# EMG.net
KiCad netlist of a schematic drawn in EAGLE
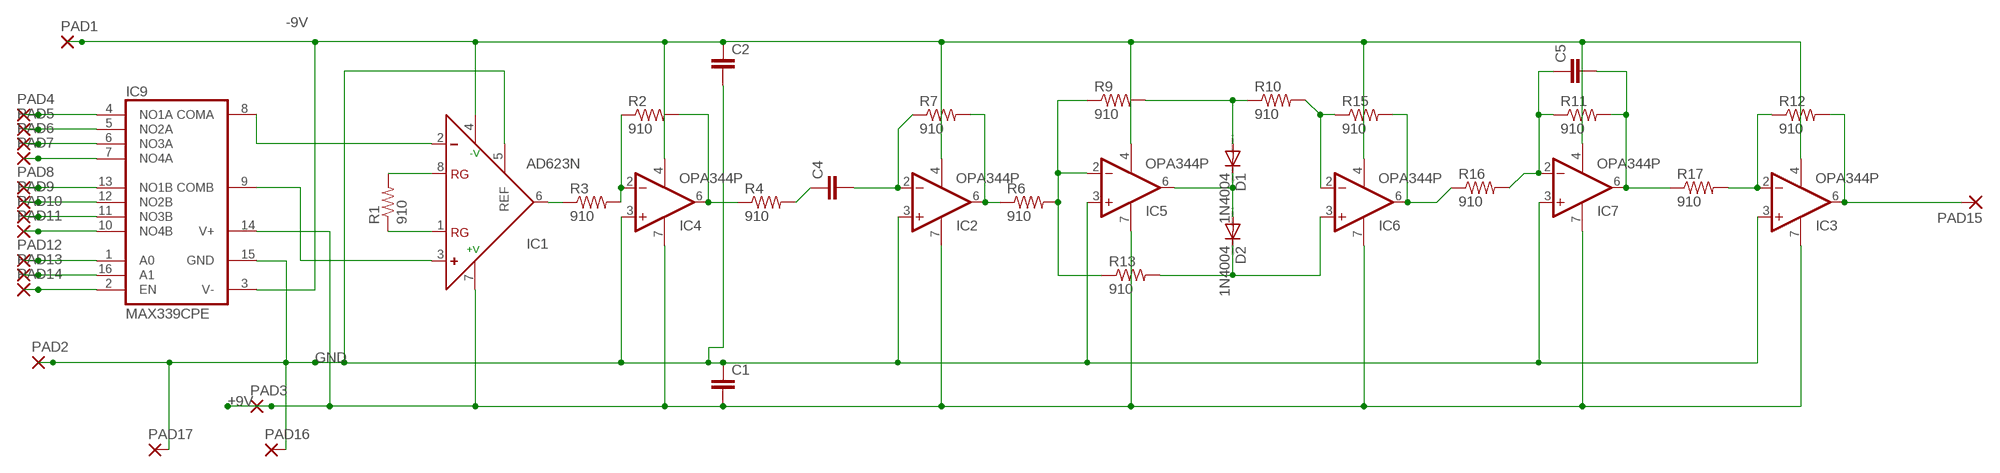
[diagram p0: schematic, sheet 1]

(export (version "E")
  (design (tool "Eeschema 10.0.6"))
  (components
    (comp (ref "C1")
      (value "C2,5-3")
      (footprint "eagle-import:C2.5-3")
      (libsource (lib "eagle-import") (part "C2,5-3"))
    )
    (comp (ref "C2")
      (value "C2,5-3")
      (footprint "eagle-import:C2.5-3")
      (libsource (lib "eagle-import") (part "C2,5-3"))
    )
    (comp (ref "C4")
      (value "C2,5-3")
      (footprint "eagle-import:C2.5-3")
      (libsource (lib "eagle-import") (part "C2,5-3"))
    )
    (comp (ref "C5")
      (value "C2,5-3")
      (footprint "eagle-import:C2.5-3")
      (libsource (lib "eagle-import") (part "C2,5-3"))
    )
    (comp (ref "D1")
      (value "1N4004")
      (footprint "eagle-import:DO41-10")
      (libsource (lib "eagle-import") (part "1N4004"))
    )
    (comp (ref "D2")
      (value "1N4004")
      (footprint "eagle-import:DO41-10")
      (libsource (lib "eagle-import") (part "1N4004"))
    )
    (comp (ref "IC1")
      (value "AD623N")
      (footprint "eagle-import:DIL08")
      (fields (field (name "MF") "ALTERA CORPORATION") (field (name "MPN") "AD623ANZ"))
      (libsource (lib "eagle-import") (part "AD623N"))
    )
    (comp (ref "IC2")
      (value "OPA344P")
      (footprint "eagle-import:DIL08")
      (libsource (lib "eagle-import") (part "OPAP344"))
    )
    (comp (ref "IC3")
      (value "OPA344P")
      (footprint "eagle-import:DIL08")
      (libsource (lib "eagle-import") (part "OPAP344"))
    )
    (comp (ref "IC4")
      (value "OPA344P")
      (footprint "eagle-import:DIL08")
      (libsource (lib "eagle-import") (part "OPAP344"))
    )
    (comp (ref "IC5")
      (value "OPA344P")
      (footprint "eagle-import:DIL08")
      (libsource (lib "eagle-import") (part "OPAP344"))
    )
    (comp (ref "IC6")
      (value "OPA344P")
      (footprint "eagle-import:DIL08")
      (libsource (lib "eagle-import") (part "OPAP344"))
    )
    (comp (ref "IC7")
      (value "OPA344P")
      (footprint "eagle-import:DIL08")
      (libsource (lib "eagle-import") (part "OPAP344"))
    )
    (comp (ref "IC9")
      (value "MAX339CPE")
      (footprint "eagle-import:DIL16")
      (fields (field (name "MPN") "MAX339CPE+"))
      (libsource (lib "eagle-import") (part "MAX339CPE"))
    )
    (comp (ref "PAD1")
      (value "2,15/1,0")
      (footprint "eagle-import:2,15_1,0")
      (libsource (lib "eagle-import") (part "2,15/1,0"))
    )
    (comp (ref "PAD2")
      (value "2,15/1,0")
      (footprint "eagle-import:2,15_1,0")
      (libsource (lib "eagle-import") (part "2,15/1,0"))
    )
    (comp (ref "PAD3")
      (value "2,15/1,0")
      (footprint "eagle-import:2,15_1,0")
      (libsource (lib "eagle-import") (part "2,15/1,0"))
    )
    (comp (ref "PAD4")
      (value "2,15/1,0")
      (footprint "eagle-import:2,15_1,0")
      (libsource (lib "eagle-import") (part "2,15/1,0"))
    )
    (comp (ref "PAD5")
      (value "2,15/1,0")
      (footprint "eagle-import:2,15_1,0")
      (libsource (lib "eagle-import") (part "2,15/1,0"))
    )
    (comp (ref "PAD6")
      (value "2,15/1,0")
      (footprint "eagle-import:2,15_1,0")
      (libsource (lib "eagle-import") (part "2,15/1,0"))
    )
    (comp (ref "PAD7")
      (value "2,15/1,0")
      (footprint "eagle-import:2,15_1,0")
      (libsource (lib "eagle-import") (part "2,15/1,0"))
    )
    (comp (ref "PAD8")
      (value "2,15/1,0")
      (footprint "eagle-import:2,15_1,0")
      (libsource (lib "eagle-import") (part "2,15/1,0"))
    )
    (comp (ref "PAD9")
      (value "2,15/1,0")
      (footprint "eagle-import:2,15_1,0")
      (libsource (lib "eagle-import") (part "2,15/1,0"))
    )
    (comp (ref "PAD10")
      (value "2,15/1,0")
      (footprint "eagle-import:2,15_1,0")
      (libsource (lib "eagle-import") (part "2,15/1,0"))
    )
    (comp (ref "PAD11")
      (value "2,15/1,0")
      (footprint "eagle-import:2,15_1,0")
      (libsource (lib "eagle-import") (part "2,15/1,0"))
    )
    (comp (ref "PAD12")
      (value "2,15/1,0")
      (footprint "eagle-import:2,15_1,0")
      (libsource (lib "eagle-import") (part "2,15/1,0"))
    )
    (comp (ref "PAD13")
      (value "2,15/1,0")
      (footprint "eagle-import:2,15_1,0")
      (libsource (lib "eagle-import") (part "2,15/1,0"))
    )
    (comp (ref "PAD14")
      (value "2,15/1,0")
      (footprint "eagle-import:2,15_1,0")
      (libsource (lib "eagle-import") (part "2,15/1,0"))
    )
    (comp (ref "PAD15")
      (value "2,15/1,0")
      (footprint "eagle-import:2,15_1,0")
      (libsource (lib "eagle-import") (part "2,15/1,0"))
    )
    (comp (ref "PAD16")
      (value "2,15/1,0")
      (footprint "eagle-import:2,15_1,0")
      (libsource (lib "eagle-import") (part "2,15/1,0"))
    )
    (comp (ref "PAD17")
      (value "2,15/1,0")
      (footprint "eagle-import:2,15_1,0")
      (libsource (lib "eagle-import") (part "2,15/1,0"))
    )
    (comp (ref "R1")
      (value "910")
      (footprint "eagle-import:0204_7")
      (libsource (lib "eagle-import") (part "R-US_0204/7"))
    )
    (comp (ref "R2")
      (value "910")
      (footprint "eagle-import:0204_7")
      (libsource (lib "eagle-import") (part "R-US_0204/7"))
    )
    (comp (ref "R3")
      (value "910")
      (footprint "eagle-import:0204_7")
      (libsource (lib "eagle-import") (part "R-US_0204/7"))
    )
    (comp (ref "R4")
      (value "910")
      (footprint "eagle-import:0204_7")
      (libsource (lib "eagle-import") (part "R-US_0204/7"))
    )
    (comp (ref "R6")
      (value "910")
      (footprint "eagle-import:0204_7")
      (libsource (lib "eagle-import") (part "R-US_0204/7"))
    )
    (comp (ref "R7")
      (value "910")
      (footprint "eagle-import:0204_7")
      (libsource (lib "eagle-import") (part "R-US_0204/7"))
    )
    (comp (ref "R9")
      (value "910")
      (footprint "eagle-import:0204_7")
      (libsource (lib "eagle-import") (part "R-US_0204/7"))
    )
    (comp (ref "R10")
      (value "910")
      (footprint "eagle-import:0204_7")
      (libsource (lib "eagle-import") (part "R-US_0204/7"))
    )
    (comp (ref "R11")
      (value "910")
      (footprint "eagle-import:0204_7")
      (libsource (lib "eagle-import") (part "R-US_0204/7"))
    )
    (comp (ref "R12")
      (value "910")
      (footprint "eagle-import:0204_7")
      (libsource (lib "eagle-import") (part "R-US_0204/7"))
    )
    (comp (ref "R13")
      (value "910")
      (footprint "eagle-import:0204_7")
      (libsource (lib "eagle-import") (part "R-US_0204/7"))
    )
    (comp (ref "R15")
      (value "910")
      (footprint "eagle-import:0204_7")
      (libsource (lib "eagle-import") (part "R-US_0204/7"))
    )
    (comp (ref "R16")
      (value "910")
      (footprint "eagle-import:0204_7")
      (libsource (lib "eagle-import") (part "R-US_0204/7"))
    )
    (comp (ref "R17")
      (value "910")
      (footprint "eagle-import:0204_7")
      (libsource (lib "eagle-import") (part "R-US_0204/7"))
    )
  )
  (nets
    (net (code "1") (name "/+9V") (class "Default")
      (node (ref "C1") (pin "2") (pinfunction "2_2") (pintype "passive"))
      (node (ref "IC1") (pin "7") (pinfunction "+V_7") (pintype "power_in"))
      (node (ref "IC2") (pin "7") (pinfunction "V+_7") (pintype "power_in"))
      (node (ref "IC3") (pin "7") (pinfunction "V+_7") (pintype "power_in"))
      (node (ref "IC4") (pin "7") (pinfunction "V+_7") (pintype "power_in"))
      (node (ref "IC5") (pin "7") (pinfunction "V+_7") (pintype "power_in"))
      (node (ref "IC6") (pin "7") (pinfunction "V+_7") (pintype "power_in"))
      (node (ref "IC7") (pin "7") (pinfunction "V+_7") (pintype "power_in"))
      (node (ref "IC9") (pin "14") (pinfunction "V+_14") (pintype "power_in"))
      (node (ref "PAD3") (pin "1") (pinfunction "P_1") (pintype "passive"))
    )
    (net (code "2") (name "/-9V") (class "Default")
      (node (ref "C2") (pin "1") (pinfunction "1_1") (pintype "passive"))
      (node (ref "IC1") (pin "4") (pinfunction "-V_4") (pintype "power_in"))
      (node (ref "IC2") (pin "4") (pinfunction "V-_4") (pintype "power_in"))
      (node (ref "IC3") (pin "4") (pinfunction "V-_4") (pintype "power_in"))
      (node (ref "IC4") (pin "4") (pinfunction "V-_4") (pintype "power_in"))
      (node (ref "IC5") (pin "4") (pinfunction "V-_4") (pintype "power_in"))
      (node (ref "IC6") (pin "4") (pinfunction "V-_4") (pintype "power_in"))
      (node (ref "IC7") (pin "4") (pinfunction "V-_4") (pintype "power_in"))
      (node (ref "IC9") (pin "3") (pinfunction "V-_3") (pintype "power_in"))
      (node (ref "PAD1") (pin "1") (pinfunction "P_1") (pintype "passive"))
    )
    (net (code "3") (name "/GND") (class "Default")
      (node (ref "C1") (pin "1") (pinfunction "1_1") (pintype "passive"))
      (node (ref "C2") (pin "2") (pinfunction "2_2") (pintype "passive"))
      (node (ref "IC1") (pin "5") (pinfunction "REF_5") (pintype "passive"))
      (node (ref "IC2") (pin "3") (pinfunction "+IN_3") (pintype "input"))
      (node (ref "IC3") (pin "3") (pinfunction "+IN_3") (pintype "input"))
      (node (ref "IC4") (pin "3") (pinfunction "+IN_3") (pintype "input"))
      (node (ref "IC5") (pin "3") (pinfunction "+IN_3") (pintype "input"))
      (node (ref "IC7") (pin "3") (pinfunction "+IN_3") (pintype "input"))
      (node (ref "IC9") (pin "15") (pinfunction "GND_15") (pintype "power_in"))
      (node (ref "PAD16") (pin "1") (pinfunction "P_1") (pintype "passive"))
      (node (ref "PAD17") (pin "1") (pinfunction "P_1") (pintype "passive"))
      (node (ref "PAD2") (pin "1") (pinfunction "P_1") (pintype "passive"))
    )
    (net (code "4") (name "Net-(C4-Pad1)") (class "Default")
      (node (ref "C4") (pin "1") (pinfunction "1_1") (pintype "passive"))
      (node (ref "R4") (pin "2") (pinfunction "2_2") (pintype "passive"))
    )
    (net (code "5") (name "Net-(D1-PadA)") (class "Default")
      (node (ref "D1") (pin "A") (pinfunction "A_A") (pintype "passive"))
      (node (ref "R10") (pin "1") (pinfunction "1_1") (pintype "passive"))
      (node (ref "R9") (pin "2") (pinfunction "2_2") (pintype "passive"))
    )
    (net (code "6") (name "Net-(IC1-+)") (class "Default")
      (node (ref "IC1") (pin "3") (pinfunction "+_3") (pintype "input"))
      (node (ref "IC9") (pin "9") (pinfunction "COMB_9") (pintype "passive"))
    )
    (net (code "7") (name "Net-(IC1--)") (class "Default")
      (node (ref "IC1") (pin "2") (pinfunction "-_2") (pintype "input"))
      (node (ref "IC9") (pin "8") (pinfunction "COMA_8") (pintype "passive"))
    )
    (net (code "8") (name "Net-(IC1-OUT)") (class "Default")
      (node (ref "IC1") (pin "6") (pinfunction "OUT_6") (pintype "output"))
      (node (ref "R3") (pin "1") (pinfunction "1_1") (pintype "passive"))
    )
    (net (code "9") (name "Net-(IC1-RG-Pad1)") (class "Default")
      (node (ref "IC1") (pin "1") (pinfunction "RG_1") (pintype "passive"))
      (node (ref "R1") (pin "1") (pinfunction "1_1") (pintype "passive"))
    )
    (net (code "10") (name "Net-(IC1-RG-Pad8)") (class "Default")
      (node (ref "IC1") (pin "8") (pinfunction "RG_8") (pintype "passive"))
      (node (ref "R1") (pin "2") (pinfunction "2_2") (pintype "passive"))
    )
    (net (code "11") (name "Net-(IC2--IN)") (class "Default")
      (node (ref "C4") (pin "2") (pinfunction "2_2") (pintype "passive"))
      (node (ref "IC2") (pin "2") (pinfunction "-IN_2") (pintype "input"))
      (node (ref "R7") (pin "1") (pinfunction "1_1") (pintype "passive"))
    )
    (net (code "12") (name "Net-(IC2-OUT)") (class "Default")
      (node (ref "IC2") (pin "6") (pinfunction "OUT_6") (pintype "output"))
      (node (ref "R6") (pin "1") (pinfunction "1_1") (pintype "passive"))
      (node (ref "R7") (pin "2") (pinfunction "2_2") (pintype "passive"))
    )
    (net (code "13") (name "Net-(IC3--IN)") (class "Default")
      (node (ref "IC3") (pin "2") (pinfunction "-IN_2") (pintype "input"))
      (node (ref "R12") (pin "1") (pinfunction "1_1") (pintype "passive"))
      (node (ref "R17") (pin "2") (pinfunction "2_2") (pintype "passive"))
    )
    (net (code "14") (name "Net-(IC3-OUT)") (class "Default")
      (node (ref "IC3") (pin "6") (pinfunction "OUT_6") (pintype "output"))
      (node (ref "PAD15") (pin "1") (pinfunction "P_1") (pintype "passive"))
      (node (ref "R12") (pin "2") (pinfunction "2_2") (pintype "passive"))
    )
    (net (code "15") (name "Net-(IC4--IN)") (class "Default")
      (node (ref "IC4") (pin "2") (pinfunction "-IN_2") (pintype "input"))
      (node (ref "R2") (pin "1") (pinfunction "1_1") (pintype "passive"))
      (node (ref "R3") (pin "2") (pinfunction "2_2") (pintype "passive"))
    )
    (net (code "16") (name "Net-(IC4-OUT)") (class "Default")
      (node (ref "IC4") (pin "6") (pinfunction "OUT_6") (pintype "output"))
      (node (ref "R2") (pin "2") (pinfunction "2_2") (pintype "passive"))
      (node (ref "R4") (pin "1") (pinfunction "1_1") (pintype "passive"))
    )
    (net (code "17") (name "Net-(IC5--IN)") (class "Default")
      (node (ref "IC5") (pin "2") (pinfunction "-IN_2") (pintype "input"))
      (node (ref "R13") (pin "1") (pinfunction "1_1") (pintype "passive"))
      (node (ref "R6") (pin "2") (pinfunction "2_2") (pintype "passive"))
      (node (ref "R9") (pin "1") (pinfunction "1_1") (pintype "passive"))
    )
    (net (code "18") (name "Net-(IC5-OUT)") (class "Default")
      (node (ref "D1") (pin "C") (pinfunction "C_C") (pintype "passive"))
      (node (ref "D2") (pin "A") (pinfunction "A_A") (pintype "passive"))
      (node (ref "IC5") (pin "6") (pinfunction "OUT_6") (pintype "output"))
    )
    (net (code "19") (name "Net-(IC6-+IN)") (class "Default")
      (node (ref "D2") (pin "C") (pinfunction "C_C") (pintype "passive"))
      (node (ref "IC6") (pin "3") (pinfunction "+IN_3") (pintype "input"))
      (node (ref "R13") (pin "2") (pinfunction "2_2") (pintype "passive"))
    )
    (net (code "20") (name "Net-(IC6--IN)") (class "Default")
      (node (ref "IC6") (pin "2") (pinfunction "-IN_2") (pintype "input"))
      (node (ref "R10") (pin "2") (pinfunction "2_2") (pintype "passive"))
      (node (ref "R15") (pin "1") (pinfunction "1_1") (pintype "passive"))
    )
    (net (code "21") (name "Net-(IC6-OUT)") (class "Default")
      (node (ref "IC6") (pin "6") (pinfunction "OUT_6") (pintype "output"))
      (node (ref "R15") (pin "2") (pinfunction "2_2") (pintype "passive"))
      (node (ref "R16") (pin "1") (pinfunction "1_1") (pintype "passive"))
    )
    (net (code "22") (name "Net-(IC7--IN)") (class "Default")
      (node (ref "C5") (pin "1") (pinfunction "1_1") (pintype "passive"))
      (node (ref "IC7") (pin "2") (pinfunction "-IN_2") (pintype "input"))
      (node (ref "R11") (pin "1") (pinfunction "1_1") (pintype "passive"))
      (node (ref "R16") (pin "2") (pinfunction "2_2") (pintype "passive"))
    )
    (net (code "23") (name "Net-(IC7-OUT)") (class "Default")
      (node (ref "C5") (pin "2") (pinfunction "2_2") (pintype "passive"))
      (node (ref "IC7") (pin "6") (pinfunction "OUT_6") (pintype "output"))
      (node (ref "R11") (pin "2") (pinfunction "2_2") (pintype "passive"))
      (node (ref "R17") (pin "1") (pinfunction "1_1") (pintype "passive"))
    )
    (net (code "24") (name "Net-(IC9-A0)") (class "Default")
      (node (ref "IC9") (pin "1") (pinfunction "A0_1") (pintype "input"))
      (node (ref "PAD12") (pin "1") (pinfunction "P_1") (pintype "passive"))
    )
    (net (code "25") (name "Net-(IC9-A1)") (class "Default")
      (node (ref "IC9") (pin "16") (pinfunction "A1_16") (pintype "input"))
      (node (ref "PAD13") (pin "1") (pinfunction "P_1") (pintype "passive"))
    )
    (net (code "26") (name "Net-(IC9-EN)") (class "Default")
      (node (ref "IC9") (pin "2") (pinfunction "EN_2") (pintype "input"))
      (node (ref "PAD14") (pin "1") (pinfunction "P_1") (pintype "passive"))
    )
    (net (code "27") (name "Net-(IC9-NO1A)") (class "Default")
      (node (ref "IC9") (pin "4") (pinfunction "NO1A_4") (pintype "passive"))
      (node (ref "PAD4") (pin "1") (pinfunction "P_1") (pintype "passive"))
    )
    (net (code "28") (name "Net-(IC9-NO1B)") (class "Default")
      (node (ref "IC9") (pin "13") (pinfunction "NO1B_13") (pintype "passive"))
      (node (ref "PAD8") (pin "1") (pinfunction "P_1") (pintype "passive"))
    )
    (net (code "29") (name "Net-(IC9-NO2A)") (class "Default")
      (node (ref "IC9") (pin "5") (pinfunction "NO2A_5") (pintype "passive"))
      (node (ref "PAD5") (pin "1") (pinfunction "P_1") (pintype "passive"))
    )
    (net (code "30") (name "Net-(IC9-NO2B)") (class "Default")
      (node (ref "IC9") (pin "12") (pinfunction "NO2B_12") (pintype "passive"))
      (node (ref "PAD9") (pin "1") (pinfunction "P_1") (pintype "passive"))
    )
    (net (code "31") (name "Net-(IC9-NO3A)") (class "Default")
      (node (ref "IC9") (pin "6") (pinfunction "NO3A_6") (pintype "passive"))
      (node (ref "PAD6") (pin "1") (pinfunction "P_1") (pintype "passive"))
    )
    (net (code "32") (name "Net-(IC9-NO3B)") (class "Default")
      (node (ref "IC9") (pin "11") (pinfunction "NO3B_11") (pintype "passive"))
      (node (ref "PAD10") (pin "1") (pinfunction "P_1") (pintype "passive"))
    )
    (net (code "33") (name "Net-(IC9-NO4A)") (class "Default")
      (node (ref "IC9") (pin "7") (pinfunction "NO4A_7") (pintype "passive"))
      (node (ref "PAD7") (pin "1") (pinfunction "P_1") (pintype "passive"))
    )
    (net (code "34") (name "Net-(IC9-NO4B)") (class "Default")
      (node (ref "IC9") (pin "10") (pinfunction "NO4B_10") (pintype "passive"))
      (node (ref "PAD11") (pin "1") (pinfunction "P_1") (pintype "passive"))
    )
  )
)
